# MEMS_LIP_Notch.net
KiCad netlist of a schematic drawn in Altium Designer
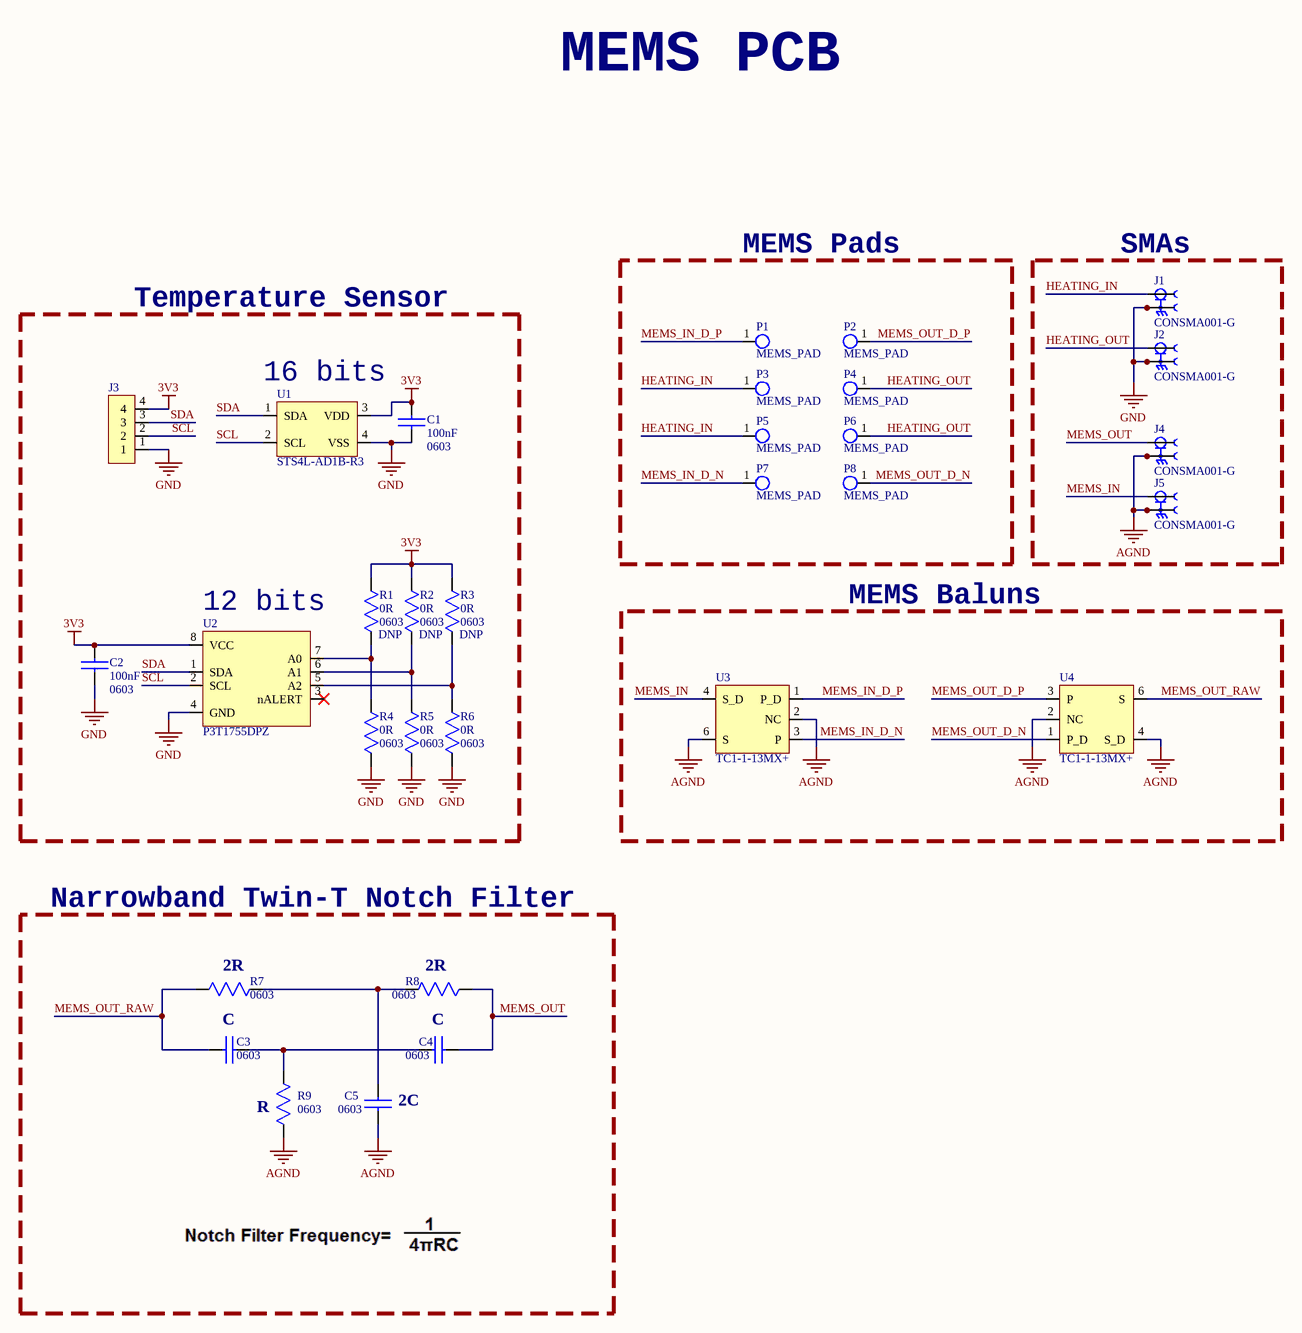
[diagram p0: MEMS_LIP+Notch.SchDoc]

(export (version "E")
  (design (tool "Eeschema 10.0.6"))
  (components
    (comp (ref "C1")
      (value "100nF")
      (footprint "C0603")
      (description "CAP CER 100NF 100V X8L 0603")
      (fields
        (field (name "MANUFACTURER") "Samsung")
        (field (name "MANUFACTURER PART NUMBER") "CL10E104KC8VPNC")
        (field (name "CASE") "0603")
      )
      (libsource (lib "MEMS_LIB") (part "CL10E104KC8VPNC"))
    )
    (comp (ref "C2")
      (value "100nF")
      (footprint "C0603")
      (description "CAP CER 100NF 100V X8L 0603")
      (fields
        (field (name "MANUFACTURER") "Samsung")
        (field (name "MANUFACTURER PART NUMBER") "CL10E104KC8VPNC")
        (field (name "CASE") "0603")
      )
      (libsource (lib "MEMS_LIB") (part "CL10E104KC8VPNC"))
    )
    (comp (ref "C3")
      (value "C0603C270J5GACTU")
      (footprint "C0603")
      (description "CAP CER 27PF 50V C0G/NP0 0603")
      (fields (field (name "PACKAGING") "0603"))
      (libsource (lib "MEMS_LIB") (part "C0603C270J5GACTU"))
    )
    (comp (ref "C4")
      (value "C0603C270J5GACTU")
      (footprint "C0603")
      (description "CAP CER 27PF 50V C0G/NP0 0603")
      (fields (field (name "PACKAGING") "0603"))
      (libsource (lib "MEMS_LIB") (part "C0603C270J5GACTU"))
    )
    (comp (ref "C5")
      (value "C0603C270J5GACTU")
      (footprint "C0603")
      (description "CAP CER 27PF 50V C0G/NP0 0603")
      (fields (field (name "PACKAGING") "0603"))
      (libsource (lib "MEMS_LIB") (part "C0603C270J5GACTU"))
    )
    (comp (ref "J1")
      (value "CONSMA001-G")
      (footprint "CONSMA001-G")
      (description "CONN SMA RCPT STR 50 OHM PCB")
      (libsource (lib "MEMS_LIB") (part "CONSMA001-G"))
    )
    (comp (ref "J2")
      (value "CONSMA001-G")
      (footprint "CONSMA001-G")
      (description "CONN SMA RCPT STR 50 OHM PCB")
      (libsource (lib "MEMS_LIB") (part "CONSMA001-G"))
    )
    (comp (ref "J3")
      (value "61300411121")
      (footprint "WURTH_61300411121")
      (description "CONN HEADER VERT 4POS 2.54MM")
      (fields (field (name "MF") "WÃ¼rth Elektronik"))
      (libsource (lib "MEMS_LIB") (part "61300411121"))
    )
    (comp (ref "J4")
      (value "CONSMA001-G")
      (footprint "CONSMA001-G")
      (description "CONN SMA RCPT STR 50 OHM PCB")
      (libsource (lib "MEMS_LIB") (part "CONSMA001-G"))
    )
    (comp (ref "J5")
      (value "CONSMA001-G")
      (footprint "CONSMA001-G")
      (description "CONN SMA RCPT STR 50 OHM PCB")
      (libsource (lib "MEMS_LIB") (part "CONSMA001-G"))
    )
    (comp (ref "P1")
      (value "MEMS_PAD")
      (footprint "MEMS_PAD")
      (description "PAD MEMS connection")
      (libsource (lib "MEMS_LIB") (part "MEMS_PAD"))
    )
    (comp (ref "P2")
      (value "MEMS_PAD")
      (footprint "MEMS_PAD")
      (description "PAD MEMS connection")
      (libsource (lib "MEMS_LIB") (part "MEMS_PAD"))
    )
    (comp (ref "P3")
      (value "MEMS_PAD")
      (footprint "MEMS_PAD")
      (description "PAD MEMS connection")
      (libsource (lib "MEMS_LIB") (part "MEMS_PAD"))
    )
    (comp (ref "P4")
      (value "MEMS_PAD")
      (footprint "MEMS_PAD")
      (description "PAD MEMS connection")
      (libsource (lib "MEMS_LIB") (part "MEMS_PAD"))
    )
    (comp (ref "P5")
      (value "MEMS_PAD")
      (footprint "MEMS_PAD")
      (description "PAD MEMS connection")
      (libsource (lib "MEMS_LIB") (part "MEMS_PAD"))
    )
    (comp (ref "P6")
      (value "MEMS_PAD")
      (footprint "MEMS_PAD")
      (description "PAD MEMS connection")
      (libsource (lib "MEMS_LIB") (part "MEMS_PAD"))
    )
    (comp (ref "P7")
      (value "MEMS_PAD")
      (footprint "MEMS_PAD")
      (description "PAD MEMS connection")
      (libsource (lib "MEMS_LIB") (part "MEMS_PAD"))
    )
    (comp (ref "P8")
      (value "MEMS_PAD")
      (footprint "MEMS_PAD")
      (description "PAD MEMS connection")
      (libsource (lib "MEMS_LIB") (part "MEMS_PAD"))
    )
    (comp (ref "R1")
      (value "0R")
      (footprint "R0603")
      (description "RES 0 OHM JUMPER 1/10W 0603")
      (fields
        (field (name "MF") "Stackpole Electronics")
        (field (name "MP") "RMCF0603ZT0R00")
        (field (name "PACKAGE") "0603")
      )
      (libsource (lib "MEMS_LIB") (part "RMCF0603ZT0R00"))
    )
    (comp (ref "R2")
      (value "0R")
      (footprint "R0603")
      (description "RES 0 OHM JUMPER 1/10W 0603")
      (fields
        (field (name "MF") "Stackpole Electronics")
        (field (name "MP") "RMCF0603ZT0R00")
        (field (name "PACKAGE") "0603")
      )
      (libsource (lib "MEMS_LIB") (part "RMCF0603ZT0R00"))
    )
    (comp (ref "R3")
      (value "0R")
      (footprint "R0603")
      (description "RES 0 OHM JUMPER 1/10W 0603")
      (fields
        (field (name "MF") "Stackpole Electronics")
        (field (name "MP") "RMCF0603ZT0R00")
        (field (name "PACKAGE") "0603")
      )
      (libsource (lib "MEMS_LIB") (part "RMCF0603ZT0R00"))
    )
    (comp (ref "R4")
      (value "0R")
      (footprint "R0603")
      (description "RES 0 OHM JUMPER 1/10W 0603")
      (fields
        (field (name "MF") "Stackpole Electronics")
        (field (name "MP") "RMCF0603ZT0R00")
        (field (name "PACKAGE") "0603")
      )
      (libsource (lib "MEMS_LIB") (part "RMCF0603ZT0R00"))
    )
    (comp (ref "R5")
      (value "0R")
      (footprint "R0603")
      (description "RES 0 OHM JUMPER 1/10W 0603")
      (fields
        (field (name "MF") "Stackpole Electronics")
        (field (name "MP") "RMCF0603ZT0R00")
        (field (name "PACKAGE") "0603")
      )
      (libsource (lib "MEMS_LIB") (part "RMCF0603ZT0R00"))
    )
    (comp (ref "R6")
      (value "0R")
      (footprint "R0603")
      (description "RES 0 OHM JUMPER 1/10W 0603")
      (fields
        (field (name "MF") "Stackpole Electronics")
        (field (name "MP") "RMCF0603ZT0R00")
        (field (name "PACKAGE") "0603")
      )
      (libsource (lib "MEMS_LIB") (part "RMCF0603ZT0R00"))
    )
    (comp (ref "R7")
      (value "RMCF0603ZT0R00")
      (footprint "R0603")
      (description "RES 0 OHM JUMPER 1/10W 0603")
      (fields (field (name "MF") "Stackpole Electronics") (field (name "PACKAGE") "0603"))
      (libsource (lib "MEMS_LIB") (part "RMCF0603ZT0R00"))
    )
    (comp (ref "R8")
      (value "RMCF0603ZT0R00")
      (footprint "R0603")
      (description "RES 0 OHM JUMPER 1/10W 0603")
      (fields (field (name "MF") "Stackpole Electronics") (field (name "PACKAGE") "0603"))
      (libsource (lib "MEMS_LIB") (part "RMCF0603ZT0R00"))
    )
    (comp (ref "R9")
      (value "RMCF0603ZT0R00")
      (footprint "R0603")
      (description "RES 0 OHM JUMPER 1/10W 0603")
      (fields (field (name "MF") "Stackpole Electronics") (field (name "PACKAGE") "0603"))
      (libsource (lib "MEMS_LIB") (part "RMCF0603ZT0R00"))
    )
    (comp (ref "U1")
      (value "STS4L-AD1B-R3")
      (footprint "STS4L-AD1B-R3")
      (description "IC - TEMPERATURE SENSOR 4-DFN")
      (libsource (lib "MEMS_LIB") (part "STS4L-AD1B-R3"))
    )
    (comp (ref "U2")
      (value "P3T1755DPZ")
      (footprint "TSSOP8_P3T1755DPZ_NXP")
      (description "SENSOR DGTL -40C ~ 125C 8-TSSOP")
      (libsource (lib "MEMS_LIB") (part "P3T1755DPZ"))
    )
    (comp (ref "U3")
      (value "TC1-1-13MX+")
      (footprint "TC1-1-13MX+")
      (description "1:1 CORE & WIRE TRANSFORMER, 4.5")
      (libsource (lib "") (part "TC1-1-13MX+_1"))
    )
    (comp (ref "U4")
      (value "TC1-1-13MX+")
      (footprint "TC1-1-13MX+")
      (description "1:1 CORE & WIRE TRANSFORMER, 4.5")
      (libsource (lib "MEMS_LIB") (part "TC1-1-13MX+"))
    )
  )
  (nets
    (net (code "1") (name "/HEATING_IN") (class "Default")
      (node (ref "J1") (pin "1") (pinfunction "1_1") (pintype "passive"))
      (node (ref "P3") (pin "1") (pinfunction "1_1") (pintype "passive"))
      (node (ref "P5") (pin "1") (pinfunction "1_1") (pintype "passive"))
    )
    (net (code "2") (name "/HEATING_OUT") (class "Default")
      (node (ref "J2") (pin "1") (pinfunction "1_1") (pintype "passive"))
      (node (ref "P4") (pin "1") (pinfunction "1_1") (pintype "passive"))
      (node (ref "P6") (pin "1") (pinfunction "1_1") (pintype "passive"))
    )
    (net (code "3") (name "/MEMS_IN") (class "Default")
      (node (ref "J5") (pin "1") (pinfunction "1_1") (pintype "passive"))
      (node (ref "U3") (pin "4") (pinfunction "S_D_4") (pintype "passive"))
    )
    (net (code "4") (name "/MEMS_IN_D_N") (class "Default")
      (node (ref "P7") (pin "1") (pinfunction "1_1") (pintype "passive"))
      (node (ref "U3") (pin "3") (pinfunction "P_3") (pintype "passive"))
    )
    (net (code "5") (name "/MEMS_IN_D_P") (class "Default")
      (node (ref "P1") (pin "1") (pinfunction "1_1") (pintype "passive"))
      (node (ref "U3") (pin "1") (pinfunction "P_D_1") (pintype "passive"))
    )
    (net (code "6") (name "/MEMS_OUT") (class "Default")
      (node (ref "C4") (pin "1") (pinfunction "1_1") (pintype "passive"))
      (node (ref "J4") (pin "1") (pinfunction "1_1") (pintype "passive"))
      (node (ref "R8") (pin "1") (pinfunction "1_1") (pintype "passive"))
    )
    (net (code "7") (name "/MEMS_OUT_D_N") (class "Default")
      (node (ref "P8") (pin "1") (pinfunction "1_1") (pintype "passive"))
      (node (ref "U4") (pin "1") (pinfunction "P_D_1") (pintype "passive"))
    )
    (net (code "8") (name "/MEMS_OUT_D_P") (class "Default")
      (node (ref "P2") (pin "1") (pinfunction "1_1") (pintype "passive"))
      (node (ref "U4") (pin "3") (pinfunction "P_3") (pintype "passive"))
    )
    (net (code "9") (name "/MEMS_OUT_RAW") (class "Default")
      (node (ref "C3") (pin "1") (pinfunction "1_1") (pintype "passive"))
      (node (ref "R7") (pin "2") (pinfunction "2_2") (pintype "passive"))
      (node (ref "U4") (pin "6") (pinfunction "S_6") (pintype "passive"))
    )
    (net (code "10") (name "/SCL") (class "Default")
      (node (ref "J3") (pin "2") (pinfunction "2_2") (pintype "passive"))
      (node (ref "U1") (pin "2") (pinfunction "SCL_2") (pintype "passive"))
      (node (ref "U2") (pin "2") (pinfunction "SCL_2") (pintype "passive"))
    )
    (net (code "11") (name "/SDA") (class "Default")
      (node (ref "J3") (pin "3") (pinfunction "3_3") (pintype "passive"))
      (node (ref "U1") (pin "1") (pinfunction "SDA_1") (pintype "passive"))
      (node (ref "U2") (pin "1") (pinfunction "SDA_1") (pintype "passive"))
    )
    (net (code "12") (name "3V3") (class "Default")
      (node (ref "C1") (pin "1") (pinfunction "1_1") (pintype "passive"))
      (node (ref "C2") (pin "1") (pinfunction "1_1") (pintype "passive"))
      (node (ref "J3") (pin "4") (pinfunction "4_4") (pintype "passive"))
      (node (ref "R1") (pin "2") (pinfunction "2_2") (pintype "passive"))
      (node (ref "R2") (pin "2") (pinfunction "2_2") (pintype "passive"))
      (node (ref "R3") (pin "2") (pinfunction "2_2") (pintype "passive"))
      (node (ref "U1") (pin "3") (pinfunction "VDD_3") (pintype "passive"))
      (node (ref "U2") (pin "8") (pinfunction "VCC_8") (pintype "power_in"))
    )
    (net (code "13") (name "AGND") (class "Default")
      (node (ref "C5") (pin "2") (pinfunction "2_2") (pintype "passive"))
      (node (ref "J4") (pin "S1") (pinfunction "2_S1") (pintype "passive"))
      (node (ref "J4") (pin "S2") (pinfunction "2_S2") (pintype "passive"))
      (node (ref "J4") (pin "S3") (pinfunction "2_S3") (pintype "passive"))
      (node (ref "J4") (pin "S4") (pinfunction "2_S4") (pintype "passive"))
      (node (ref "J5") (pin "S1") (pinfunction "2_S1") (pintype "passive"))
      (node (ref "J5") (pin "S2") (pinfunction "2_S2") (pintype "passive"))
      (node (ref "J5") (pin "S3") (pinfunction "2_S3") (pintype "passive"))
      (node (ref "J5") (pin "S4") (pinfunction "2_S4") (pintype "passive"))
      (node (ref "R9") (pin "2") (pinfunction "2_2") (pintype "passive"))
      (node (ref "U3") (pin "2") (pinfunction "NC_2") (pintype "passive"))
      (node (ref "U3") (pin "6") (pinfunction "S_6") (pintype "passive"))
      (node (ref "U4") (pin "2") (pinfunction "NC_2") (pintype "passive"))
      (node (ref "U4") (pin "4") (pinfunction "S_D_4") (pintype "passive"))
    )
    (net (code "14") (name "GND") (class "Default")
      (node (ref "C1") (pin "2") (pinfunction "2_2") (pintype "passive"))
      (node (ref "C2") (pin "2") (pinfunction "2_2") (pintype "passive"))
      (node (ref "J1") (pin "S1") (pinfunction "2_S1") (pintype "passive"))
      (node (ref "J1") (pin "S2") (pinfunction "2_S2") (pintype "passive"))
      (node (ref "J1") (pin "S3") (pinfunction "2_S3") (pintype "passive"))
      (node (ref "J1") (pin "S4") (pinfunction "2_S4") (pintype "passive"))
      (node (ref "J2") (pin "S1") (pinfunction "2_S1") (pintype "passive"))
      (node (ref "J2") (pin "S2") (pinfunction "2_S2") (pintype "passive"))
      (node (ref "J2") (pin "S3") (pinfunction "2_S3") (pintype "passive"))
      (node (ref "J2") (pin "S4") (pinfunction "2_S4") (pintype "passive"))
      (node (ref "J3") (pin "1") (pinfunction "1_1") (pintype "passive"))
      (node (ref "R4") (pin "1") (pinfunction "1_1") (pintype "passive"))
      (node (ref "R5") (pin "1") (pinfunction "1_1") (pintype "passive"))
      (node (ref "R6") (pin "1") (pinfunction "1_1") (pintype "passive"))
      (node (ref "U1") (pin "4") (pinfunction "VSS_4") (pintype "passive"))
      (node (ref "U2") (pin "4") (pinfunction "GND_4") (pintype "power_in"))
    )
    (net (code "15") (name "Net-(C3-Pad2)") (class "Default")
      (node (ref "C3") (pin "2") (pinfunction "2_2") (pintype "passive"))
      (node (ref "C4") (pin "2") (pinfunction "2_2") (pintype "passive"))
      (node (ref "R9") (pin "1") (pinfunction "1_1") (pintype "passive"))
    )
    (net (code "16") (name "Net-(C5-Pad1)") (class "Default")
      (node (ref "C5") (pin "1") (pinfunction "1_1") (pintype "passive"))
      (node (ref "R7") (pin "1") (pinfunction "1_1") (pintype "passive"))
      (node (ref "R8") (pin "2") (pinfunction "2_2") (pintype "passive"))
    )
    (net (code "17") (name "Net-(U2-A0)") (class "Default")
      (node (ref "R1") (pin "1") (pinfunction "1_1") (pintype "passive"))
      (node (ref "R4") (pin "2") (pinfunction "2_2") (pintype "passive"))
      (node (ref "U2") (pin "7") (pinfunction "A0_7") (pintype "passive"))
    )
    (net (code "18") (name "Net-(U2-A1)") (class "Default")
      (node (ref "R2") (pin "1") (pinfunction "1_1") (pintype "passive"))
      (node (ref "R5") (pin "2") (pinfunction "2_2") (pintype "passive"))
      (node (ref "U2") (pin "6") (pinfunction "A1_6") (pintype "passive"))
    )
    (net (code "19") (name "Net-(U2-A2)") (class "Default")
      (node (ref "R3") (pin "1") (pinfunction "1_1") (pintype "passive"))
      (node (ref "R6") (pin "2") (pinfunction "2_2") (pintype "passive"))
      (node (ref "U2") (pin "5") (pinfunction "A2_5") (pintype "passive"))
    )
    (net (code "20") (name "unconnected-(U2-nALERT-Pad3)") (class "Default")
      (node (ref "U2") (pin "3") (pinfunction "nALERT_3") (pintype "passive+no_connect"))
    )
  )
)
